# LightSwitch-USB.net
KiCad netlist of a schematic drawn in EAGLE
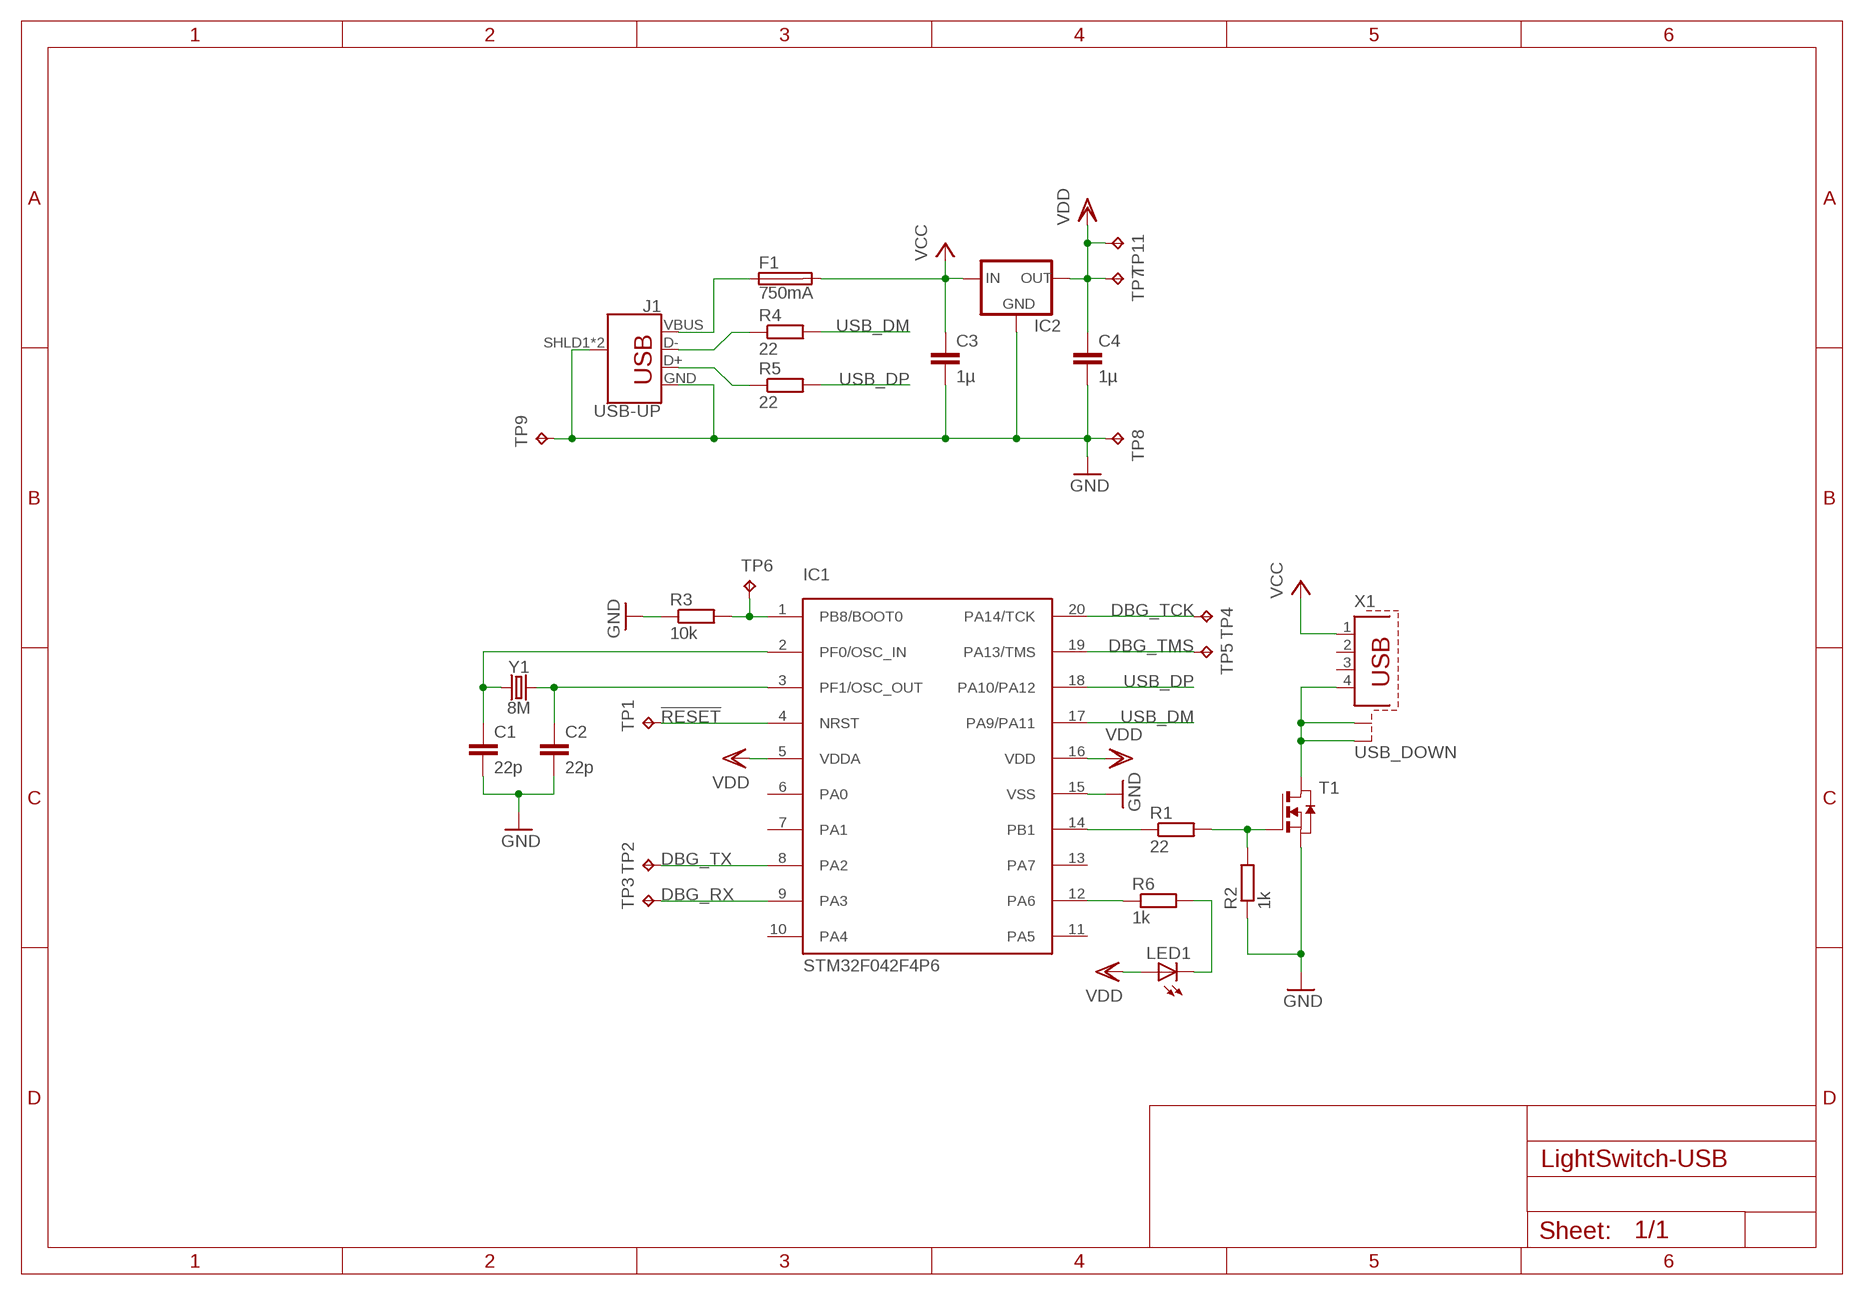
[diagram p0: schematic, sheet 1]

(export (version "E")
  (design (tool "Eeschema 10.0.6"))
  (components
    (comp (ref "C1")
      (value "22p")
      (footprint "eagle-import:C0603")
      (libsource (lib "eagle-import") (part "C-EUC0603"))
    )
    (comp (ref "C2")
      (value "22p")
      (footprint "eagle-import:C0603")
      (libsource (lib "eagle-import") (part "C-EUC0603"))
    )
    (comp (ref "C3")
      (value "1µ")
      (footprint "eagle-import:C0603")
      (libsource (lib "eagle-import") (part "C-EUC0603"))
    )
    (comp (ref "C4")
      (value "1µ")
      (footprint "eagle-import:C0603")
      (libsource (lib "eagle-import") (part "C-EUC0603"))
    )
    (comp (ref "F1")
      (value "750mA")
      (footprint "eagle-import:R1206")
      (libsource (lib "eagle-import") (part "FUSER1206"))
    )
    (comp (ref "IC1")
      (value "STM32F042F4P6")
      (footprint "eagle-import:TSSOP20")
      (libsource (lib "eagle-import") (part "STM32F042F?6P4"))
    )
    (comp (ref "IC2")
      (value "XC63FPM")
      (footprint "eagle-import:SOT23")
      (libsource (lib "eagle-import") (part "XC63FPM"))
    )
    (comp (ref "J1")
      (value "USB-UP")
      (footprint "eagle-import:USB-A-H")
      (libsource (lib "eagle-import") (part "USB_A_PTH_MALE"))
    )
    (comp (ref "LED1")
      (value "LEDCHIP-LED0805")
      (footprint "eagle-import:CHIP-LED0805")
      (libsource (lib "eagle-import") (part "LEDCHIP-LED0805"))
    )
    (comp (ref "R1")
      (value "22")
      (footprint "eagle-import:R0603")
      (libsource (lib "eagle-import") (part "R-EU_R0603"))
    )
    (comp (ref "R2")
      (value "1k")
      (footprint "eagle-import:R0603")
      (libsource (lib "eagle-import") (part "R-EU_R0603"))
    )
    (comp (ref "R3")
      (value "10k")
      (footprint "eagle-import:R0603")
      (libsource (lib "eagle-import") (part "R-EU_R0603"))
    )
    (comp (ref "R4")
      (value "22")
      (footprint "eagle-import:R0603")
      (libsource (lib "eagle-import") (part "R-EU_R0603"))
    )
    (comp (ref "R5")
      (value "22")
      (footprint "eagle-import:R0603")
      (libsource (lib "eagle-import") (part "R-EU_R0603"))
    )
    (comp (ref "R6")
      (value "1k")
      (footprint "eagle-import:R0603")
      (libsource (lib "eagle-import") (part "R-EU_R0603"))
    )
    (comp (ref "T1")
      (value "NMOSSOT23")
      (footprint "eagle-import:SOT-23")
      (libsource (lib "eagle-import") (part "NMOSSOT23"))
    )
    (comp (ref "TP1")
      (value "TPB1,27")
      (footprint "eagle-import:B1,27")
      (libsource (lib "eagle-import") (part "TPB1,27"))
    )
    (comp (ref "TP2")
      (value "TPB1,27")
      (footprint "eagle-import:B1,27")
      (libsource (lib "eagle-import") (part "TPB1,27"))
    )
    (comp (ref "TP3")
      (value "TPB1,27")
      (footprint "eagle-import:B1,27")
      (libsource (lib "eagle-import") (part "TPB1,27"))
    )
    (comp (ref "TP4")
      (value "TPB1,27")
      (footprint "eagle-import:B1,27")
      (libsource (lib "eagle-import") (part "TPB1,27"))
    )
    (comp (ref "TP5")
      (value "TPB1,27")
      (footprint "eagle-import:B1,27")
      (libsource (lib "eagle-import") (part "TPB1,27"))
    )
    (comp (ref "TP6")
      (value "TPB1,27")
      (footprint "eagle-import:B1,27")
      (libsource (lib "eagle-import") (part "TPB1,27"))
    )
    (comp (ref "TP7")
      (value "TPB1,27")
      (footprint "eagle-import:B1,27")
      (libsource (lib "eagle-import") (part "TPB1,27"))
    )
    (comp (ref "TP8")
      (value "TPB1,27")
      (footprint "eagle-import:B1,27")
      (libsource (lib "eagle-import") (part "TPB1,27"))
    )
    (comp (ref "TP9")
      (value "TPB1,27")
      (footprint "eagle-import:B1,27")
      (libsource (lib "eagle-import") (part "TPB1,27"))
    )
    (comp (ref "TP11")
      (value "TPB1,27")
      (footprint "eagle-import:B1,27")
      (libsource (lib "eagle-import") (part "TPB1,27"))
    )
    (comp (ref "X1")
      (value "USB_DOWN")
      (footprint "eagle-import:PN87520-S")
      (libsource (lib "eagle-import") (part "PN87520-S"))
    )
    (comp (ref "Y1")
      (value "8M")
      (footprint "eagle-import:CRYSTAL-SMD-5X3.2-2PAD")
      (libsource (lib "eagle-import") (part "CRYSTALSMD-5X3.2-2PAD"))
    )
  )
  (nets
    (net (code "1") (name "/DBG_RX") (class "Default")
      (node (ref "IC1") (pin "9") (pinfunction "PA3_9") (pintype "bidirectional"))
      (node (ref "TP3") (pin "TP") (pinfunction "TP_TP") (pintype "input"))
    )
    (net (code "2") (name "/DBG_TCK") (class "Default")
      (node (ref "IC1") (pin "20") (pinfunction "PA14/TCK_20") (pintype "bidirectional"))
      (node (ref "TP4") (pin "TP") (pinfunction "TP_TP") (pintype "input"))
    )
    (net (code "3") (name "/DBG_TMS") (class "Default")
      (node (ref "IC1") (pin "19") (pinfunction "PA13/TMS_19") (pintype "bidirectional"))
      (node (ref "TP5") (pin "TP") (pinfunction "TP_TP") (pintype "input"))
    )
    (net (code "4") (name "/DBG_TX") (class "Default")
      (node (ref "IC1") (pin "8") (pinfunction "PA2_8") (pintype "bidirectional"))
      (node (ref "TP2") (pin "TP") (pinfunction "TP_TP") (pintype "input"))
    )
    (net (code "5") (name "/USB_DM") (class "Default")
      (node (ref "IC1") (pin "17") (pinfunction "PA9/PA11_17") (pintype "bidirectional"))
      (node (ref "R4") (pin "2") (pinfunction "2_2") (pintype "passive"))
    )
    (net (code "6") (name "/USB_DP") (class "Default")
      (node (ref "IC1") (pin "18") (pinfunction "PA10/PA12_18") (pintype "bidirectional"))
      (node (ref "R5") (pin "2") (pinfunction "2_2") (pintype "passive"))
    )
    (net (code "7") (name "/~{RESET}") (class "Default")
      (node (ref "IC1") (pin "4") (pinfunction "NRST_4") (pintype "bidirectional"))
      (node (ref "TP1") (pin "TP") (pinfunction "TP_TP") (pintype "input"))
    )
    (net (code "8") (name "GND") (class "Default")
      (node (ref "C1") (pin "2") (pinfunction "2_2") (pintype "passive"))
      (node (ref "C2") (pin "2") (pinfunction "2_2") (pintype "passive"))
      (node (ref "C3") (pin "2") (pinfunction "2_2") (pintype "passive"))
      (node (ref "C4") (pin "2") (pinfunction "2_2") (pintype "passive"))
      (node (ref "IC1") (pin "15") (pinfunction "VSS_15") (pintype "bidirectional"))
      (node (ref "IC2") (pin "1") (pinfunction "GND_1") (pintype "input"))
      (node (ref "J1") (pin "GND") (pinfunction "GND_GND") (pintype "power_in"))
      (node (ref "J1") (pin "SHLD1") (pinfunction "SHIELD_SHLD1") (pintype "bidirectional"))
      (node (ref "J1") (pin "SHLD2") (pinfunction "SHIELD_SHLD2") (pintype "bidirectional"))
      (node (ref "R2") (pin "1") (pinfunction "1_1") (pintype "passive"))
      (node (ref "R3") (pin "1") (pinfunction "1_1") (pintype "passive"))
      (node (ref "T1") (pin "2") (pinfunction "S_2") (pintype "passive"))
      (node (ref "TP8") (pin "TP") (pinfunction "TP_TP") (pintype "input"))
      (node (ref "TP9") (pin "TP") (pinfunction "TP_TP") (pintype "input"))
    )
    (net (code "9") (name "Net-(F1-Pad1)") (class "Default")
      (node (ref "F1") (pin "1") (pinfunction "1_1") (pintype "passive"))
      (node (ref "J1") (pin "VBUS") (pinfunction "VBUS_VBUS") (pintype "power_in"))
    )
    (net (code "10") (name "Net-(IC1-PA6)") (class "Default")
      (node (ref "IC1") (pin "12") (pinfunction "PA6_12") (pintype "bidirectional"))
      (node (ref "R6") (pin "1") (pinfunction "1_1") (pintype "passive"))
    )
    (net (code "11") (name "Net-(IC1-PB1)") (class "Default")
      (node (ref "IC1") (pin "14") (pinfunction "PB1_14") (pintype "bidirectional"))
      (node (ref "R1") (pin "1") (pinfunction "1_1") (pintype "passive"))
    )
    (net (code "12") (name "Net-(IC1-PB8{slash}BOOT0)") (class "Default")
      (node (ref "IC1") (pin "1") (pinfunction "PB8/BOOT0_1") (pintype "bidirectional"))
      (node (ref "R3") (pin "2") (pinfunction "2_2") (pintype "passive"))
      (node (ref "TP6") (pin "TP") (pinfunction "TP_TP") (pintype "input"))
    )
    (net (code "13") (name "Net-(IC1-PF0{slash}OSC_IN)") (class "Default")
      (node (ref "C1") (pin "1") (pinfunction "1_1") (pintype "passive"))
      (node (ref "IC1") (pin "2") (pinfunction "PF0/OSC_IN_2") (pintype "bidirectional"))
      (node (ref "Y1") (pin "P$1") (pinfunction "1_P$1") (pintype "passive"))
    )
    (net (code "14") (name "Net-(IC1-PF1{slash}OSC_OUT)") (class "Default")
      (node (ref "C2") (pin "1") (pinfunction "1_1") (pintype "passive"))
      (node (ref "IC1") (pin "3") (pinfunction "PF1/OSC_OUT_3") (pintype "bidirectional"))
      (node (ref "Y1") (pin "P$2") (pinfunction "2_P$2") (pintype "passive"))
    )
    (net (code "15") (name "Net-(J1-PadD+)") (class "Default")
      (node (ref "J1") (pin "D+") (pinfunction "D+_D+") (pintype "bidirectional"))
      (node (ref "R5") (pin "1") (pinfunction "1_1") (pintype "passive"))
    )
    (net (code "16") (name "Net-(J1-PadD-)") (class "Default")
      (node (ref "J1") (pin "D-") (pinfunction "D-_D-") (pintype "bidirectional"))
      (node (ref "R4") (pin "1") (pinfunction "1_1") (pintype "passive"))
    )
    (net (code "17") (name "Net-(LED1-PadC)") (class "Default")
      (node (ref "LED1") (pin "C") (pinfunction "C_C") (pintype "passive"))
      (node (ref "R6") (pin "2") (pinfunction "2_2") (pintype "passive"))
    )
    (net (code "18") (name "Net-(T1-D)") (class "Default")
      (node (ref "T1") (pin "1") (pinfunction "D_1") (pintype "passive"))
      (node (ref "X1") (pin "4") (pinfunction "4_4") (pintype "passive"))
      (node (ref "X1") (pin "S1") (pinfunction "S1_S1") (pintype "passive"))
      (node (ref "X1") (pin "S2") (pinfunction "S2_S2") (pintype "passive"))
    )
    (net (code "19") (name "Net-(T1-G)") (class "Default")
      (node (ref "R1") (pin "2") (pinfunction "2_2") (pintype "passive"))
      (node (ref "R2") (pin "2") (pinfunction "2_2") (pintype "passive"))
      (node (ref "T1") (pin "3") (pinfunction "G_3") (pintype "passive"))
    )
    (net (code "20") (name "VCC") (class "Default")
      (node (ref "C3") (pin "1") (pinfunction "1_1") (pintype "passive"))
      (node (ref "F1") (pin "2") (pinfunction "2_2") (pintype "passive"))
      (node (ref "IC2") (pin "3") (pinfunction "IN_3") (pintype "input"))
      (node (ref "X1") (pin "1") (pinfunction "1_1") (pintype "passive"))
    )
    (net (code "21") (name "VDD") (class "Default")
      (node (ref "C4") (pin "1") (pinfunction "1_1") (pintype "passive"))
      (node (ref "IC1") (pin "16") (pinfunction "VDD_16") (pintype "bidirectional"))
      (node (ref "IC1") (pin "5") (pinfunction "VDDA_5") (pintype "bidirectional"))
      (node (ref "IC2") (pin "2") (pinfunction "OUT_2") (pintype "passive"))
      (node (ref "LED1") (pin "A") (pinfunction "A_A") (pintype "passive"))
      (node (ref "TP11") (pin "TP") (pinfunction "TP_TP") (pintype "input"))
      (node (ref "TP7") (pin "TP") (pinfunction "TP_TP") (pintype "input"))
    )
    (net (code "22") (name "unconnected-(IC1-PA0-Pad6)") (class "Default")
      (node (ref "IC1") (pin "6") (pinfunction "PA0_6") (pintype "bidirectional"))
    )
    (net (code "23") (name "unconnected-(IC1-PA1-Pad7)") (class "Default")
      (node (ref "IC1") (pin "7") (pinfunction "PA1_7") (pintype "bidirectional"))
    )
    (net (code "24") (name "unconnected-(IC1-PA4-Pad10)") (class "Default")
      (node (ref "IC1") (pin "10") (pinfunction "PA4_10") (pintype "bidirectional"))
    )
    (net (code "25") (name "unconnected-(IC1-PA5-Pad11)") (class "Default")
      (node (ref "IC1") (pin "11") (pinfunction "PA5_11") (pintype "bidirectional"))
    )
    (net (code "26") (name "unconnected-(IC1-PA7-Pad13)") (class "Default")
      (node (ref "IC1") (pin "13") (pinfunction "PA7_13") (pintype "bidirectional"))
    )
    (net (code "27") (name "unconnected-(X1-Pad2)") (class "Default")
      (node (ref "X1") (pin "2") (pinfunction "2_2") (pintype "passive"))
    )
    (net (code "28") (name "unconnected-(X1-Pad3)") (class "Default")
      (node (ref "X1") (pin "3") (pinfunction "3_3") (pintype "passive"))
    )
  )
)
